# RFTP1812.net
KiCad netlist of a schematic drawn in Altium Designer
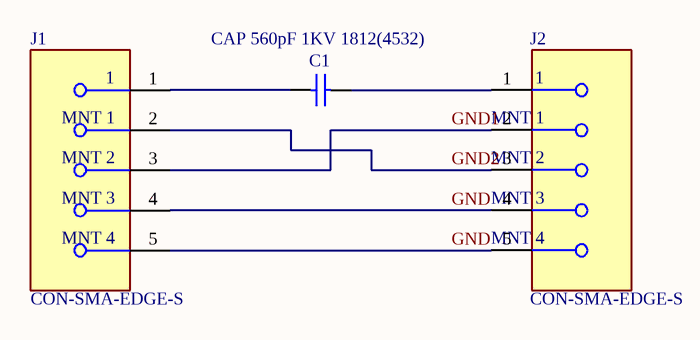
[diagram p0: RFTP1812.SchDoc]

(export (version "E")
  (design (tool "Eeschema 10.0.6"))
  (components
    (comp (ref "C1")
      (value "CAP 560pF 1KV 1812(4532)")
      (footprint "CAPC1812(4532)230_M")
      (description "CAP 560pF 1KV ±10% 1812 (4532 Metric) Thickness 2.3mm SMD")
      (fields (field (name "TOLERANCE") "Â±10%"))
      (libsource (lib "Altium Content Vault") (part "CAP"))
    )
    (comp (ref "J1")
      (value "CON-SMA-EDGE-S")
      (footprint "FP-CON-SMA-EDGE-S-MFG")
      (description "CONN SMA JACK STR EDGE MNT")
      (fields
        (field (name "OCTOPART") "https://octopart.com/con-sma-edge-s-rf+solutions-70967450")
        (field (name "MANUFACTURER") "RF Solutions Ltd.")
      )
      (libsource (lib "") (part "a163d97a771fcdd2fd1f1a9264c171f_1"))
    )
    (comp (ref "J2")
      (value "CON-SMA-EDGE-S")
      (footprint "FP-CON-SMA-EDGE-S-MFG")
      (description "CONN SMA JACK STR EDGE MNT")
      (fields
        (field (name "OCTOPART") "https://octopart.com/con-sma-edge-s-rf+solutions-70967450")
        (field (name "MANUFACTURER") "RF Solutions Ltd.")
      )
      (libsource (lib "Altium Content Vault") (part "a163d97a771fcdd2fd1f1a9264c171f"))
    )
  )
  (nets
    (net (code "1") (name "/GND") (class "Default")
      (node (ref "J1") (pin "4") (pinfunction "MNT_3_4") (pintype "passive"))
      (node (ref "J1") (pin "5") (pinfunction "MNT_4_5") (pintype "passive"))
      (node (ref "J2") (pin "4") (pinfunction "MNT_3_4") (pintype "passive"))
      (node (ref "J2") (pin "5") (pinfunction "MNT_4_5") (pintype "passive"))
    )
    (net (code "2") (name "/GND1") (class "Default")
      (node (ref "J1") (pin "3") (pinfunction "MNT_2_3") (pintype "passive"))
      (node (ref "J2") (pin "2") (pinfunction "MNT_1_2") (pintype "passive"))
    )
    (net (code "3") (name "/GND2") (class "Default")
      (node (ref "J1") (pin "2") (pinfunction "MNT_1_2") (pintype "passive"))
      (node (ref "J2") (pin "3") (pinfunction "MNT_2_3") (pintype "passive"))
    )
    (net (code "4") (name "Net-(C1-Pad1)") (class "Default")
      (node (ref "C1") (pin "1") (pinfunction "1_1") (pintype "passive"))
      (node (ref "J1") (pin "1") (pinfunction "1_1") (pintype "passive"))
    )
    (net (code "5") (name "Net-(C1-Pad2)") (class "Default")
      (node (ref "C1") (pin "2") (pinfunction "2_2") (pintype "passive"))
      (node (ref "J2") (pin "1") (pinfunction "1_1") (pintype "passive"))
    )
  )
)
